# BLDC_driver.net
KiCad netlist of a schematic drawn in Altium Designer
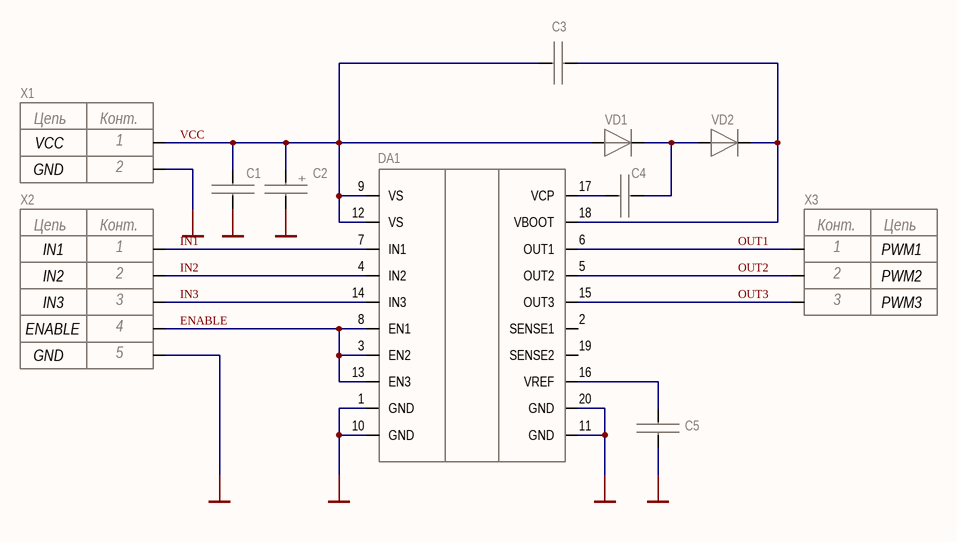
[diagram p0: BLDC_driver.SchDoc]

(export (version "E")
  (design (tool "Eeschema 10.0.6"))
  (components
    (comp (ref "C1")
      (value "C_0.1uF")
      (footprint "component_lib:CAP_1206")
      (libsource (lib "component_lib") (part "C_0.1uF"))
    )
    (comp (ref "C2")
      (value "C_POL_100uF_25V")
      (footprint "component_lib:CAP_EL_100uF_25V")
      (libsource (lib "component_lib") (part "C_POL_100uF_25V"))
    )
    (comp (ref "C3")
      (value "C_0.22uF")
      (footprint "component_lib:CAP_1206")
      (libsource (lib "component_lib") (part "C_0.22uF"))
    )
    (comp (ref "C4")
      (value "C_10nF")
      (footprint "component_lib:CAP_1206")
      (libsource (lib "component_lib") (part "C_10nF"))
    )
    (comp (ref "C5")
      (value "C_1uF")
      (footprint "component_lib:CAP_1206")
      (libsource (lib "component_lib") (part "C_1uF"))
    )
    (comp (ref "DA1")
      (value "L6234PD")
      (footprint "component_lib:POWERSO-20")
      (libsource (lib "component_lib") (part "L6234PD"))
    )
    (comp (ref "VD1")
      (value "VD_1N4148WS")
      (footprint "component_lib:SOD323")
      (libsource (lib "component_lib") (part "VD_1N4148WS"))
    )
    (comp (ref "VD2")
      (value "VD_1N4148WS")
      (footprint "component_lib:SOD323")
      (libsource (lib "component_lib") (part "VD_1N4148WS"))
    )
    (comp (ref "X1")
      (value "TERMINAL_BLOCK")
      (footprint "component_lib:Terminal_Block_2x")
      (libsource (lib "component_lib") (part "TERMINAL_BLOCK"))
    )
    (comp (ref "X2")
      (value "PLS5")
      (footprint "component_lib:PLS5")
      (libsource (lib "component_lib") (part "PLS5"))
    )
    (comp (ref "X3")
      (value "PLS3")
      (footprint "component_lib:PLS3")
      (libsource (lib "component_lib") (part "PLS3"))
    )
  )
  (nets
    (net (code "1") (name "/ENABLE") (class "Default")
      (node (ref "DA1") (pin "13") (pinfunction "EN3_13") (pintype "passive"))
      (node (ref "DA1") (pin "3") (pinfunction "EN2_3") (pintype "passive"))
      (node (ref "DA1") (pin "8") (pinfunction "EN1_8") (pintype "passive"))
      (node (ref "X2") (pin "4") (pinfunction "ENABLE_4") (pintype "passive"))
    )
    (net (code "2") (name "/IN1") (class "Default")
      (node (ref "DA1") (pin "7") (pinfunction "IN1_7") (pintype "passive"))
      (node (ref "X2") (pin "1") (pinfunction "IN1_1") (pintype "passive"))
    )
    (net (code "3") (name "/IN2") (class "Default")
      (node (ref "DA1") (pin "4") (pinfunction "IN2_4") (pintype "passive"))
      (node (ref "X2") (pin "2") (pinfunction "IN2_2") (pintype "passive"))
    )
    (net (code "4") (name "/IN3") (class "Default")
      (node (ref "DA1") (pin "14") (pinfunction "IN3_14") (pintype "passive"))
      (node (ref "X2") (pin "3") (pinfunction "IN3_3") (pintype "passive"))
    )
    (net (code "5") (name "/OUT1") (class "Default")
      (node (ref "DA1") (pin "6") (pinfunction "OUT1_6") (pintype "passive"))
      (node (ref "X3") (pin "1") (pinfunction "PWM1_1") (pintype "passive"))
    )
    (net (code "6") (name "/OUT2") (class "Default")
      (node (ref "DA1") (pin "5") (pinfunction "OUT2_5") (pintype "passive"))
      (node (ref "X3") (pin "2") (pinfunction "PWM2_2") (pintype "passive"))
    )
    (net (code "7") (name "/OUT3") (class "Default")
      (node (ref "DA1") (pin "15") (pinfunction "OUT3_15") (pintype "passive"))
      (node (ref "X3") (pin "3") (pinfunction "PWM3_3") (pintype "passive"))
    )
    (net (code "8") (name "/VCC") (class "Default")
      (node (ref "C1") (pin "2") (pinfunction "2_2") (pintype "passive"))
      (node (ref "C2") (pin "1") (pinfunction "1_1") (pintype "passive"))
      (node (ref "C3") (pin "1") (pinfunction "1_1") (pintype "passive"))
      (node (ref "DA1") (pin "12") (pinfunction "VS_12") (pintype "passive"))
      (node (ref "DA1") (pin "9") (pinfunction "VS_9") (pintype "passive"))
      (node (ref "VD1") (pin "1") (pinfunction "1_1") (pintype "passive"))
      (node (ref "X1") (pin "1") (pinfunction "VCC_1") (pintype "passive"))
    )
    (net (code "9") (name "GND") (class "Default")
      (node (ref "C1") (pin "1") (pinfunction "1_1") (pintype "passive"))
      (node (ref "C2") (pin "2") (pinfunction "2_2") (pintype "passive"))
      (node (ref "C5") (pin "1") (pinfunction "1_1") (pintype "passive"))
      (node (ref "DA1") (pin "1") (pinfunction "GND_1") (pintype "passive"))
      (node (ref "DA1") (pin "10") (pinfunction "GND_10") (pintype "passive"))
      (node (ref "DA1") (pin "11") (pinfunction "GND_11") (pintype "passive"))
      (node (ref "DA1") (pin "20") (pinfunction "GND_20") (pintype "passive"))
      (node (ref "X1") (pin "2") (pinfunction "GND_2") (pintype "passive"))
      (node (ref "X2") (pin "5") (pinfunction "GND_5") (pintype "passive"))
    )
    (net (code "10") (name "Net-(C4-Pad2)") (class "Default")
      (node (ref "C4") (pin "2") (pinfunction "2_2") (pintype "passive"))
      (node (ref "VD1") (pin "2") (pinfunction "2_2") (pintype "passive"))
      (node (ref "VD2") (pin "1") (pinfunction "1_1") (pintype "passive"))
    )
    (net (code "11") (name "Net-(DA1-VBOOT)") (class "Default")
      (node (ref "C3") (pin "2") (pinfunction "2_2") (pintype "passive"))
      (node (ref "DA1") (pin "18") (pinfunction "VBOOT_18") (pintype "passive"))
      (node (ref "VD2") (pin "2") (pinfunction "2_2") (pintype "passive"))
    )
    (net (code "12") (name "Net-(DA1-VCP)") (class "Default")
      (node (ref "C4") (pin "1") (pinfunction "1_1") (pintype "passive"))
      (node (ref "DA1") (pin "17") (pinfunction "VCP_17") (pintype "passive"))
    )
    (net (code "13") (name "Net-(DA1-VREF)") (class "Default")
      (node (ref "C5") (pin "2") (pinfunction "2_2") (pintype "passive"))
      (node (ref "DA1") (pin "16") (pinfunction "VREF_16") (pintype "passive"))
    )
    (net (code "14") (name "unconnected-(DA1-SENSE1-Pad2)") (class "Default")
      (node (ref "DA1") (pin "2") (pinfunction "SENSE1_2") (pintype "passive"))
    )
    (net (code "15") (name "unconnected-(DA1-SENSE2-Pad19)") (class "Default")
      (node (ref "DA1") (pin "19") (pinfunction "SENSE2_19") (pintype "passive"))
    )
  )
)
